# Ctrol1_Ctrol2.net
KiCad netlist of a schematic drawn in Altium Designer
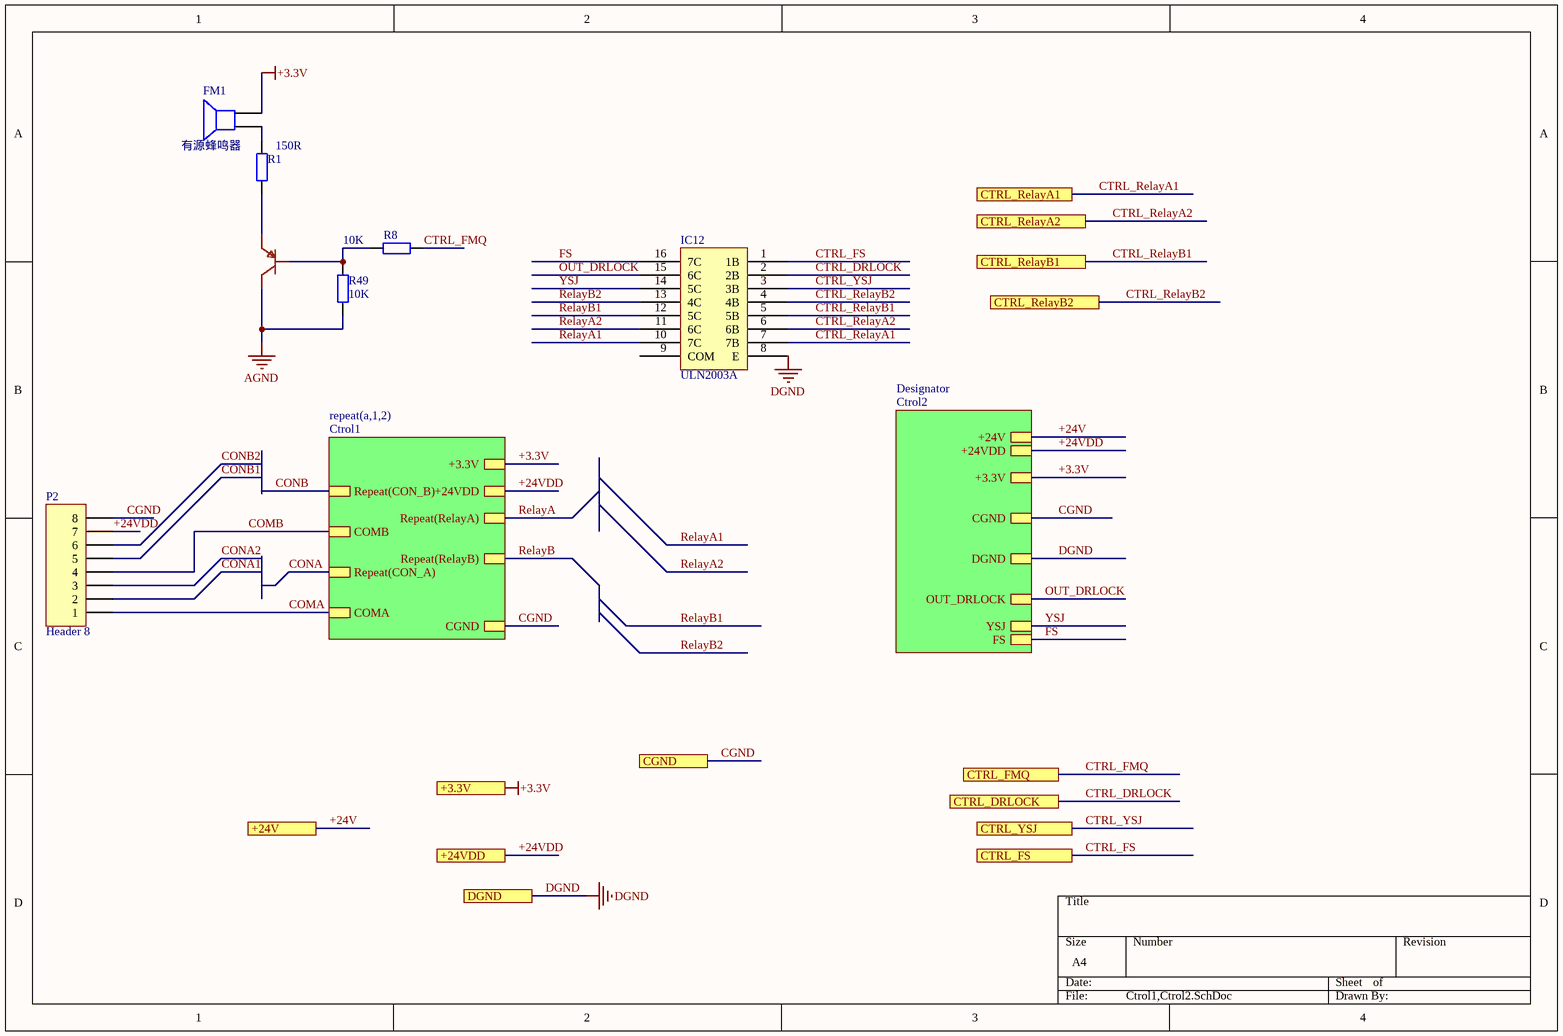
[diagram p0: Ctrol1,Ctrol2.SchDoc]

(export (version "E")
  (design (tool "Eeschema 10.0.6"))
  (components
    (comp (ref "FM1") (value "有源蜂鸣器") (footprint "SPK") (libsource (lib "Documents") (part "Speaker")))
    (comp (ref "IC12") (value "ULN2003A") (footprint "SO16") (libsource (lib "Documents") (part "ULN2003")))
    (comp (ref "P2")
      (value "Header 8")
      (footprint "CONN-TH-KF7.62-8p")
      (description "DG141V-2.54-8")
      (fields (field (name "PUBLISHER") "Altium Limited"))
      (libsource (lib "Miscellaneous Connectors") (part "Header 8"))
    )
    (comp (ref "Q3")
      (value "SS8550")
      (footprint "SOT23")
      (fields (field (name "MANUFACTURER") "宏迦橙"))
      (libsource (lib "main board fo stk_1") (part "SS8550_C7420371"))
    )
    (comp (ref "R1")
      (value "150R")
      (footprint "0805R")
      (description "Resistor")
      (fields (field (name "PUBLISHER") "Altium Limited"))
      (libsource (lib "") (part "Res2_2"))
    )
    (comp (ref "R8")
      (value "10K")
      (footprint "0805R")
      (description "Resistor")
      (fields (field (name "PUBLISHER") "Altium Limited"))
      (libsource (lib "") (part "Res2_1"))
    )
    (comp (ref "R49")
      (value "10K")
      (footprint "0805R")
      (description "Resistor")
      (fields (field (name "PUBLISHER") "Altium Limited"))
      (libsource (lib "Miscellaneous Devices") (part "Res2"))
    )
  )
  (nets
    (net (code "1") (name "+3.3V") (class "Default")
      (node (ref "FM1") (pin "2") (pinfunction "2_2") (pintype "passive"))
    )
    (net (code "3") (name "/+24VDD") (class "Default")
      (node (ref "P2") (pin "7") (pinfunction "7_7") (pintype "passive"))
    )
    (net (code "4") (name "/CGND") (class "Default")
      (node (ref "P2") (pin "8") (pinfunction "8_8") (pintype "passive"))
    )
    (net (code "5") (name "/COMA") (class "Default")
      (node (ref "P2") (pin "1") (pinfunction "1_1") (pintype "passive"))
    )
    (net (code "6") (name "/COMB") (class "Default")
      (node (ref "P2") (pin "4") (pinfunction "4_4") (pintype "passive"))
    )
    (net (code "8") (name "/CONA1") (class "Default")
      (node (ref "P2") (pin "2") (pinfunction "2_2") (pintype "passive"))
    )
    (net (code "9") (name "/CONA2") (class "Default")
      (node (ref "P2") (pin "3") (pinfunction "3_3") (pintype "passive"))
    )
    (net (code "11") (name "/CONB1") (class "Default")
      (node (ref "P2") (pin "5") (pinfunction "5_5") (pintype "passive"))
    )
    (net (code "12") (name "/CONB2") (class "Default")
      (node (ref "P2") (pin "6") (pinfunction "6_6") (pintype "passive"))
    )
    (net (code "13") (name "/CTRL_DRLOCK") (class "Default")
      (node (ref "IC12") (pin "2") (pinfunction "2B_2") (pintype "passive"))
    )
    (net (code "14") (name "/CTRL_FMQ") (class "Default")
      (node (ref "R8") (pin "2") (pinfunction "2_2") (pintype "passive"))
    )
    (net (code "15") (name "/CTRL_FS") (class "Default")
      (node (ref "IC12") (pin "1") (pinfunction "1B_1") (pintype "passive"))
    )
    (net (code "16") (name "/CTRL_RelayA1") (class "Default")
      (node (ref "IC12") (pin "7") (pinfunction "7B_7") (pintype "passive"))
    )
    (net (code "17") (name "/CTRL_RelayA2") (class "Default")
      (node (ref "IC12") (pin "6") (pinfunction "6B_6") (pintype "passive"))
    )
    (net (code "18") (name "/CTRL_RelayB1") (class "Default")
      (node (ref "IC12") (pin "5") (pinfunction "5B_5") (pintype "passive"))
    )
    (net (code "19") (name "/CTRL_RelayB2") (class "Default")
      (node (ref "IC12") (pin "4") (pinfunction "4B_4") (pintype "passive"))
    )
    (net (code "20") (name "/CTRL_YSJ") (class "Default")
      (node (ref "IC12") (pin "3") (pinfunction "3B_3") (pintype "passive"))
    )
    (net (code "21") (name "/FS") (class "Default")
      (node (ref "IC12") (pin "16") (pinfunction "7C_16") (pintype "passive"))
    )
    (net (code "22") (name "/OUT_DRLOCK") (class "Default")
      (node (ref "IC12") (pin "15") (pinfunction "6C_15") (pintype "passive"))
    )
    (net (code "24") (name "/RelayA1") (class "Default")
      (node (ref "IC12") (pin "10") (pinfunction "7C_10") (pintype "passive"))
    )
    (net (code "25") (name "/RelayA2") (class "Default")
      (node (ref "IC12") (pin "11") (pinfunction "6C_11") (pintype "passive"))
    )
    (net (code "27") (name "/RelayB1") (class "Default")
      (node (ref "IC12") (pin "12") (pinfunction "5C_12") (pintype "passive"))
    )
    (net (code "28") (name "/RelayB2") (class "Default")
      (node (ref "IC12") (pin "13") (pinfunction "4C_13") (pintype "passive"))
    )
    (net (code "29") (name "/YSJ") (class "Default")
      (node (ref "IC12") (pin "14") (pinfunction "5C_14") (pintype "passive"))
    )
    (net (code "30") (name "AGND") (class "Default")
      (node (ref "Q3") (pin "3") (pinfunction "C_3") (pintype "passive"))
      (node (ref "R49") (pin "2") (pinfunction "2_2") (pintype "passive"))
    )
    (net (code "31") (name "DGND") (class "Default")
      (node (ref "IC12") (pin "8") (pinfunction "E_8") (pintype "passive"))
    )
    (net (code "32") (name "Net-(FM1-Pad1)") (class "Default")
      (node (ref "FM1") (pin "1") (pinfunction "1_1") (pintype "passive"))
      (node (ref "R1") (pin "2") (pinfunction "2_2") (pintype "passive"))
    )
    (net (code "33") (name "Net-(Q3-B)") (class "Default")
      (node (ref "Q3") (pin "1") (pinfunction "B_1") (pintype "passive"))
      (node (ref "R49") (pin "1") (pinfunction "1_1") (pintype "passive"))
      (node (ref "R8") (pin "1") (pinfunction "1_1") (pintype "passive"))
    )
    (net (code "34") (name "Net-(Q3-E)") (class "Default")
      (node (ref "Q3") (pin "2") (pinfunction "E_2") (pintype "passive"))
      (node (ref "R1") (pin "1") (pinfunction "1_1") (pintype "passive"))
    )
    (net (code "35") (name "unconnected-(IC12-COM-Pad9)") (class "Default")
      (node (ref "IC12") (pin "9") (pinfunction "COM_9") (pintype "passive"))
    )
  )
)
